# MaUWB.net
KiCad netlist of a schematic drawn in Altium Designer
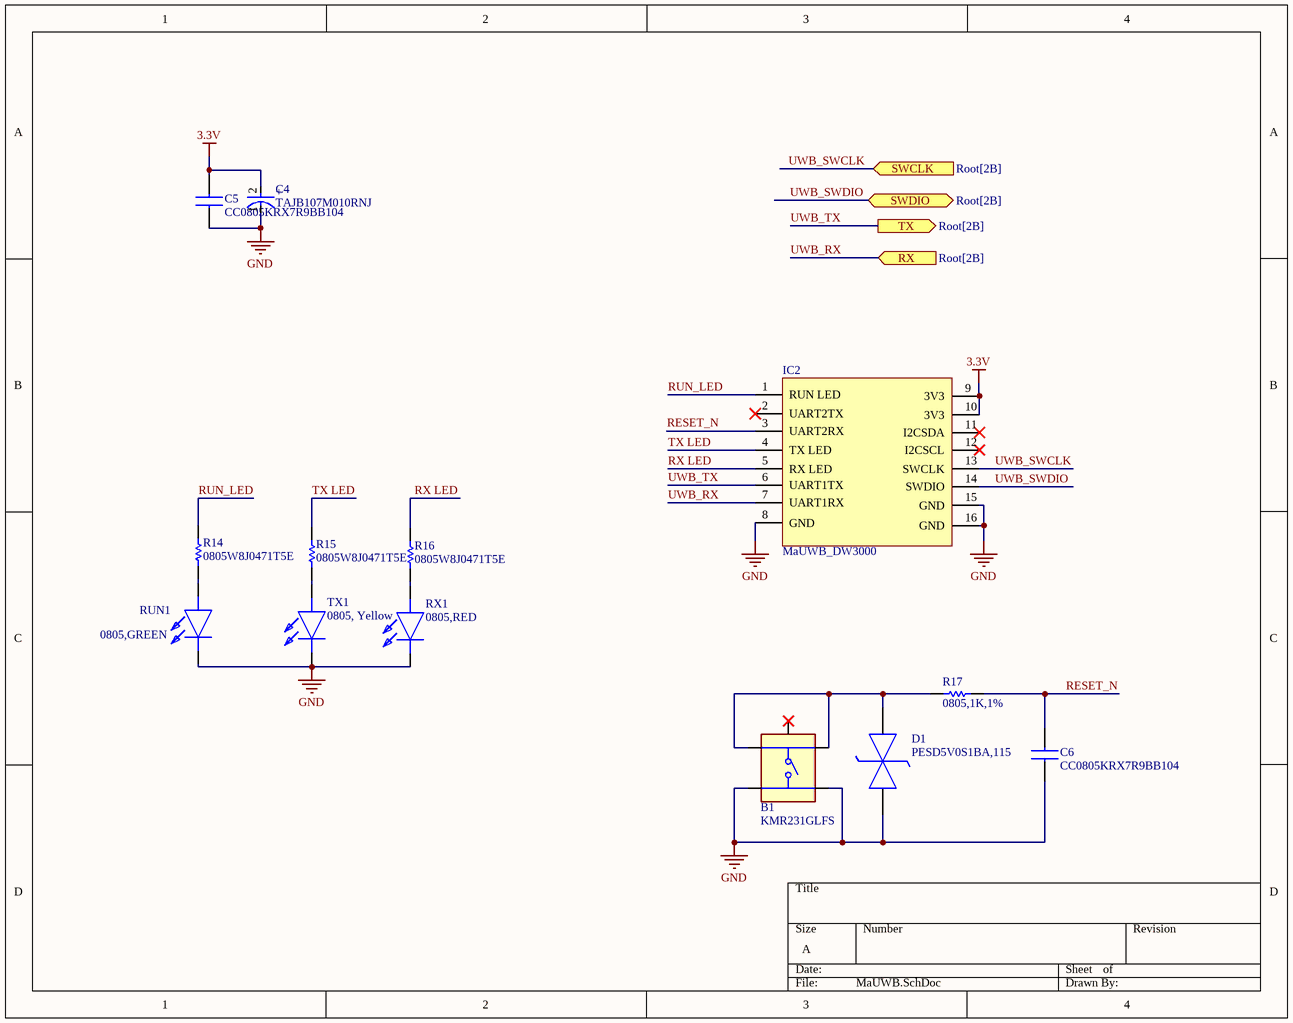
[diagram p0: MaUWB.SchDoc]

(export (version "E")
  (design (tool "Eeschema 10.0.6"))
  (components
    (comp (ref "B1")
      (value "KMR231GLFS")
      (footprint "KMR231GLFS")
      (description "Tactile Switch SPST 300gf 1.9mm Gull Wing 4.6mm x 2.8mm Surface Mount")
      (fields (field (name "LCSC PART #") "C99271"))
      (libsource (lib "MaUWB") (part "KMR231GLFS"))
    )
    (comp (ref "C4")
      (value "TAJB107M010RNJ")
      (footprint "CAPPM3528X210N")
      (description "100uF, Tantalum")
      (fields (field (name "LCSC PART #") "C7196"))
      (libsource (lib "MaUWB") (part "TAJB107M010RNJ"))
    )
    (comp (ref "C5")
      (value "CC0805KRX7R9BB104")
      (footprint "CAPC2012X95N")
      (description "100nF, 0805, X7R")
      (fields (field (name "LCSC PART #") "C49678"))
      (libsource (lib "MaUWB") (part "CC0805KRX7R9BB104"))
    )
    (comp (ref "C6")
      (value "CC0805KRX7R9BB104")
      (footprint "CAPC2012X95N")
      (description "100nF, 0805, X7R")
      (fields (field (name "LCSC PART #") "C49678"))
      (libsource (lib "MaUWB") (part "CC0805KRX7R9BB104"))
    )
    (comp (ref "D1")
      (value "PESD5V0S1BA,115")
      (footprint "SOD2512X110N")
      (description "14VC Clamp 12A@8/20us Ipp ESD DIODE SOD-323")
      (fields (field (name "LCSC PART #") "C19224"))
      (libsource (lib "MaUWB") (part "PESD5V0S1BA,115"))
    )
    (comp (ref "IC2")
      (value "MaUWB_DW3000")
      (footprint "MaUWB_DW3000:MaUWB_DW3000")
      (libsource (lib "MaUWB_DW3000") (part "MaUWB_DW3000"))
    )
    (comp (ref "R14")
      (value "0805W8J0471T5E")
      (footprint "RESC2013X65N - Duplicate")
      (description "470, 0805, 5%")
      (fields (field (name "LCSC PART #") "C17710") (field (name "MANU PART #") "0805W8F4700T5E"))
      (libsource (lib "MaUWB") (part "0805W8J0471T5E"))
    )
    (comp (ref "R15")
      (value "0805W8J0471T5E")
      (footprint "RESC2013X65N - Duplicate")
      (description "470, 0805, 5%")
      (fields (field (name "LCSC PART #") "C17710") (field (name "MANU PART #") "0805W8F4700T5E"))
      (libsource (lib "MaUWB") (part "0805W8J0471T5E"))
    )
    (comp (ref "R16")
      (value "0805W8J0471T5E")
      (footprint "RESC2013X65N - Duplicate")
      (description "470, 0805, 5%")
      (fields (field (name "LCSC PART #") "C17710") (field (name "MANU PART #") "0805W8F4700T5E"))
      (libsource (lib "MaUWB") (part "0805W8J0471T5E"))
    )
    (comp (ref "R17")
      (value "0805,1K,1%")
      (footprint "RESC2013X65N - Duplicate2")
      (fields (field (name "MANU PART #") "0805W8F1001T5E") (field (name "LCSC PART #") "C17513"))
      (libsource (lib "MaUWB") (part "0805W8F1001T5E"))
    )
    (comp (ref "RUN1")
      (value "0805,GREEN")
      (footprint "LEDC2012X120N")
      (description "Green 569nm LED Indication - Discrete 2.1V 0805 (2012 Metric)")
      (fields
        (field (name "MANUFACTURER_PART_NUMBER") "LTST-C170GKT")
        (field (name "MOUSER PART NUMBER") "859-LTST-C170GKT")
      )
      (libsource (lib "MaUWB") (part "LTST-C170GKT"))
    )
    (comp (ref "RX1")
      (value "0805,RED")
      (footprint "LEDC2012X120N - Duplicate")
      (description "Red 631nm LED Indication - Discrete 2V 0805 (2012 Metric)")
      (fields
        (field (name "MANUFACTURER_PART_NUMBER") "LTST-C170KRKT")
        (field (name "MOUSER PART NUMBER") "859-LTST-C170KRKT")
      )
      (libsource (lib "MaUWB") (part "LTST-C170KRKT"))
    )
    (comp (ref "TX1")
      (value "0805, Yellow")
      (footprint "LEDC2012X120N - Duplicate")
      (description "Yellow 631nm LED Indication - Discrete 2V 0805 (2012 Metric)")
      (fields (field (name "MANU PART #") "KT-0603W") (field (name "LCSC PART #") "C2290"))
      (libsource (lib "MaUWB") (part "KT-0603W"))
    )
  )
  (nets
    (net (code "1") (name "/RESET_N") (class "Default")
      (node (ref "C6") (pin "2") (pinfunction "2_2") (pintype "passive"))
      (node (ref "IC2") (pin "3") (pinfunction "UART2RX_3") (pintype "passive"))
      (node (ref "R17") (pin "2") (pinfunction "2_2") (pintype "passive"))
    )
    (net (code "2") (name "/RUN_LED") (class "Default")
      (node (ref "IC2") (pin "1") (pinfunction "RUN_LED_1") (pintype "passive"))
      (node (ref "R14") (pin "2") (pinfunction "2_2") (pintype "passive"))
    )
    (net (code "3") (name "/RX LED") (class "Default")
      (node (ref "IC2") (pin "5") (pinfunction "RX_LED_5") (pintype "passive"))
      (node (ref "R16") (pin "2") (pinfunction "2_2") (pintype "passive"))
    )
    (net (code "4") (name "/TX LED") (class "Default")
      (node (ref "IC2") (pin "4") (pinfunction "TX_LED_4") (pintype "passive"))
      (node (ref "R15") (pin "2") (pinfunction "2_2") (pintype "passive"))
    )
    (net (code "5") (name "/UWB_RX") (class "Default")
      (node (ref "IC2") (pin "7") (pinfunction "UART1RX_7") (pintype "passive"))
    )
    (net (code "6") (name "/UWB_SWCLK") (class "Default")
      (node (ref "IC2") (pin "13") (pinfunction "SWCLK_13") (pintype "passive"))
    )
    (net (code "7") (name "/UWB_SWDIO") (class "Default")
      (node (ref "IC2") (pin "14") (pinfunction "SWDIO_14") (pintype "passive"))
    )
    (net (code "8") (name "/UWB_TX") (class "Default")
      (node (ref "IC2") (pin "6") (pinfunction "UART1TX_6") (pintype "passive"))
    )
    (net (code "9") (name "3.3V") (class "Default")
      (node (ref "C4") (pin "2") (pinfunction "A_2") (pintype "passive"))
      (node (ref "C5") (pin "2") (pinfunction "2_2") (pintype "passive"))
      (node (ref "IC2") (pin "10") (pinfunction "3V3_10") (pintype "passive"))
      (node (ref "IC2") (pin "9") (pinfunction "3V3_9") (pintype "passive"))
    )
    (net (code "10") (name "GND") (class "Default")
      (node (ref "B1") (pin "3") (pinfunction "3_3") (pintype "passive"))
      (node (ref "B1") (pin "4") (pinfunction "4_4") (pintype "passive"))
      (node (ref "C4") (pin "1") (pinfunction "C_1") (pintype "passive"))
      (node (ref "C5") (pin "1") (pinfunction "1_1") (pintype "passive"))
      (node (ref "C6") (pin "1") (pinfunction "1_1") (pintype "passive"))
      (node (ref "D1") (pin "1") (pinfunction "K1_1") (pintype "passive"))
      (node (ref "IC2") (pin "15") (pinfunction "GND_15") (pintype "passive"))
      (node (ref "IC2") (pin "16") (pinfunction "GND_16") (pintype "passive"))
      (node (ref "IC2") (pin "8") (pinfunction "GND_8") (pintype "passive"))
      (node (ref "RUN1") (pin "1") (pinfunction "K_1") (pintype "passive"))
      (node (ref "RX1") (pin "1") (pinfunction "K_1") (pintype "passive"))
      (node (ref "TX1") (pin "1") (pinfunction "K_1") (pintype "passive"))
    )
    (net (code "11") (name "Net-(D1-K2)") (class "Default")
      (node (ref "B1") (pin "1") (pinfunction "1_1") (pintype "passive"))
      (node (ref "B1") (pin "2") (pinfunction "2_2") (pintype "passive"))
      (node (ref "D1") (pin "2") (pinfunction "K2_2") (pintype "passive"))
      (node (ref "R17") (pin "1") (pinfunction "1_1") (pintype "passive"))
    )
    (net (code "12") (name "Net-(RUN1-A)") (class "Default")
      (node (ref "R14") (pin "1") (pinfunction "1_1") (pintype "passive"))
      (node (ref "RUN1") (pin "2") (pinfunction "A_2") (pintype "passive"))
    )
    (net (code "13") (name "Net-(RX1-A)") (class "Default")
      (node (ref "R16") (pin "1") (pinfunction "1_1") (pintype "passive"))
      (node (ref "RX1") (pin "2") (pinfunction "A_2") (pintype "passive"))
    )
    (net (code "14") (name "Net-(TX1-A)") (class "Default")
      (node (ref "R15") (pin "1") (pinfunction "1_1") (pintype "passive"))
      (node (ref "TX1") (pin "2") (pinfunction "A_2") (pintype "passive"))
    )
    (net (code "15") (name "unconnected-(B1-Pad5)") (class "Default")
      (node (ref "B1") (pin "5") (pinfunction "5_5") (pintype "passive+no_connect"))
    )
    (net (code "16") (name "unconnected-(IC2-I2CSCL-Pad12)") (class "Default")
      (node (ref "IC2") (pin "12") (pinfunction "I2CSCL_12") (pintype "passive+no_connect"))
    )
    (net (code "17") (name "unconnected-(IC2-I2CSDA-Pad11)") (class "Default")
      (node (ref "IC2") (pin "11") (pinfunction "I2CSDA_11") (pintype "passive+no_connect"))
    )
    (net (code "18") (name "unconnected-(IC2-UART2TX-Pad2)") (class "Default")
      (node (ref "IC2") (pin "2") (pinfunction "UART2TX_2") (pintype "passive+no_connect"))
    )
  )
)
